# pga460_direct.net
KiCad netlist of a schematic drawn in EAGLE
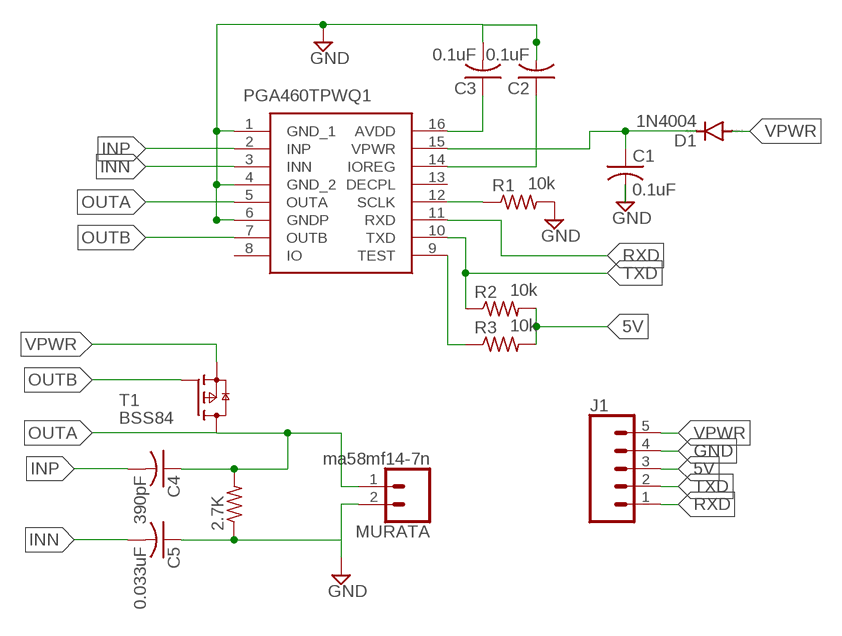
[diagram p0: schematic, sheet 1]

(export (version "E")
  (design (tool "Eeschema 10.0.6"))
  (components
    (comp (ref "2.7K")
      (value "R-US_M0805")
      (footprint "eagle-import:M0805")
      (libsource (lib "eagle-import") (part "R-US_M0805"))
    )
    (comp (ref "C1")
      (value "0.1uF")
      (footprint "eagle-import:C0805")
      (libsource (lib "eagle-import") (part "C-USC0805"))
    )
    (comp (ref "C2")
      (value "0.1uF")
      (footprint "eagle-import:C0805")
      (libsource (lib "eagle-import") (part "C-USC0805"))
    )
    (comp (ref "C3")
      (value "0.1uF")
      (footprint "eagle-import:C0805")
      (libsource (lib "eagle-import") (part "C-USC0805"))
    )
    (comp (ref "C4")
      (value "390pF")
      (footprint "eagle-import:C0805")
      (libsource (lib "eagle-import") (part "C-USC0805"))
    )
    (comp (ref "C5")
      (value "0.033uF")
      (footprint "eagle-import:C0805")
      (libsource (lib "eagle-import") (part "C-USC0805"))
    )
    (comp (ref "D1")
      (value "1N4004")
      (footprint "eagle-import:DO41-10")
      (libsource (lib "eagle-import") (part "1N4004"))
    )
    (comp (ref "IC1")
      (value "PGA460TPWQ1")
      (footprint "eagle-import:SOP65P640X120-16N")
      (fields (field (name "MOUSER_PART_NUMBER") "595-PGA460TPWQ1"))
      (libsource (lib "eagle-import") (part "PGA460TPWQ1"))
    )
    (comp (ref "J1")
      (value "CONN_05")
      (footprint "eagle-import:1X05")
      (libsource (lib "eagle-import") (part "CONN_05"))
    )
    (comp (ref "MURATA")
      (value "ma58mf14-7n")
      (footprint "eagle-import:1X02_LOCK")
      (libsource (lib "eagle-import") (part "CONN_02LOCK"))
    )
    (comp (ref "R1")
      (value "10k")
      (footprint "eagle-import:R0805")
      (libsource (lib "eagle-import") (part "R-US_R0805"))
    )
    (comp (ref "R2")
      (value "10k")
      (footprint "eagle-import:R0805")
      (libsource (lib "eagle-import") (part "R-US_R0805"))
    )
    (comp (ref "R3")
      (value "10k")
      (footprint "eagle-import:R0805")
      (libsource (lib "eagle-import") (part "R-US_R0805"))
    )
    (comp (ref "T1")
      (value "BSS84")
      (footprint "eagle-import:SOT23")
      (libsource (lib "eagle-import") (part "BSS84"))
    )
  )
  (nets
    (net (code "1") (name "5V") (class "Default")
      (node (ref "J1") (pin "3") (pinfunction "3_3") (pintype "passive"))
      (node (ref "R2") (pin "2") (pinfunction "2_2") (pintype "passive"))
      (node (ref "R3") (pin "2") (pinfunction "2_2") (pintype "passive"))
    )
    (net (code "2") (name "GND") (class "Default")
      (node (ref "2.7K") (pin "1") (pinfunction "1_1") (pintype "passive"))
      (node (ref "C1") (pin "2") (pinfunction "2_2") (pintype "passive"))
      (node (ref "C2") (pin "2") (pinfunction "2_2") (pintype "passive"))
      (node (ref "C3") (pin "2") (pinfunction "2_2") (pintype "passive"))
      (node (ref "C5") (pin "1") (pinfunction "1_1") (pintype "passive"))
      (node (ref "IC1") (pin "1") (pinfunction "GND_1_1") (pintype "power_in"))
      (node (ref "IC1") (pin "4") (pinfunction "GND_2_4") (pintype "power_in"))
      (node (ref "IC1") (pin "6") (pinfunction "GNDP_6") (pintype "power_in"))
      (node (ref "J1") (pin "4") (pinfunction "4_4") (pintype "passive"))
      (node (ref "MURATA") (pin "2") (pinfunction "2_2") (pintype "passive"))
      (node (ref "R1") (pin "2") (pinfunction "2_2") (pintype "passive"))
    )
    (net (code "3") (name "INN") (class "Default")
      (node (ref "C5") (pin "2") (pinfunction "2_2") (pintype "passive"))
      (node (ref "IC1") (pin "3") (pinfunction "INN_3") (pintype "input"))
    )
    (net (code "4") (name "INP") (class "Default")
      (node (ref "C4") (pin "2") (pinfunction "2_2") (pintype "passive"))
      (node (ref "IC1") (pin "2") (pinfunction "INP_2") (pintype "input"))
    )
    (net (code "5") (name "Net-(IC1-AVDD)") (class "Default")
      (node (ref "C3") (pin "1") (pinfunction "1_1") (pintype "passive"))
      (node (ref "IC1") (pin "16") (pinfunction "AVDD_16") (pintype "power_in"))
    )
    (net (code "6") (name "Net-(IC1-IOREG)") (class "Default")
      (node (ref "C2") (pin "1") (pinfunction "1_1") (pintype "passive"))
      (node (ref "IC1") (pin "14") (pinfunction "IOREG_14") (pintype "power_in"))
    )
    (net (code "7") (name "Net-(IC1-SCLK)") (class "Default")
      (node (ref "IC1") (pin "12") (pinfunction "SCLK_12") (pintype "input"))
      (node (ref "R1") (pin "1") (pinfunction "1_1") (pintype "passive"))
    )
    (net (code "8") (name "Net-(IC1-TEST)") (class "Default")
      (node (ref "IC1") (pin "9") (pinfunction "TEST_9") (pintype "bidirectional"))
      (node (ref "R3") (pin "1") (pinfunction "1_1") (pintype "passive"))
    )
    (net (code "9") (name "Net-(IC1-VPWR)") (class "Default")
      (node (ref "C1") (pin "1") (pinfunction "1_1") (pintype "passive"))
      (node (ref "D1") (pin "C") (pinfunction "C_C") (pintype "passive"))
      (node (ref "IC1") (pin "15") (pinfunction "VPWR_15") (pintype "power_in"))
    )
    (net (code "10") (name "OUTA") (class "Default")
      (node (ref "2.7K") (pin "2") (pinfunction "2_2") (pintype "passive"))
      (node (ref "C4") (pin "1") (pinfunction "1_1") (pintype "passive"))
      (node (ref "IC1") (pin "5") (pinfunction "OUTA_5") (pintype "output"))
      (node (ref "MURATA") (pin "1") (pinfunction "1_1") (pintype "passive"))
      (node (ref "T1") (pin "3") (pinfunction "D_3") (pintype "passive"))
    )
    (net (code "11") (name "OUTB") (class "Default")
      (node (ref "IC1") (pin "7") (pinfunction "OUTB_7") (pintype "output"))
      (node (ref "T1") (pin "1") (pinfunction "G_1") (pintype "passive"))
    )
    (net (code "12") (name "RXD") (class "Default")
      (node (ref "IC1") (pin "11") (pinfunction "RXD_11") (pintype "input"))
      (node (ref "J1") (pin "1") (pinfunction "1_1") (pintype "passive"))
    )
    (net (code "13") (name "TXD") (class "Default")
      (node (ref "IC1") (pin "10") (pinfunction "TXD_10") (pintype "output"))
      (node (ref "J1") (pin "2") (pinfunction "2_2") (pintype "passive"))
      (node (ref "R2") (pin "1") (pinfunction "1_1") (pintype "passive"))
    )
    (net (code "14") (name "VPWR") (class "Default")
      (node (ref "D1") (pin "A") (pinfunction "A_A") (pintype "passive"))
      (node (ref "J1") (pin "5") (pinfunction "5_5") (pintype "passive"))
      (node (ref "T1") (pin "2") (pinfunction "S_2") (pintype "passive"))
    )
    (net (code "15") (name "unconnected-(IC1-DECPL-Pad13)") (class "Default")
      (node (ref "IC1") (pin "13") (pinfunction "DECPL_13") (pintype "output"))
    )
    (net (code "16") (name "unconnected-(IC1-IO-Pad8)") (class "Default")
      (node (ref "IC1") (pin "8") (pinfunction "IO_8") (pintype "bidirectional"))
    )
  )
)
